# puente_h.net
KiCad netlist of a schematic drawn in EAGLE
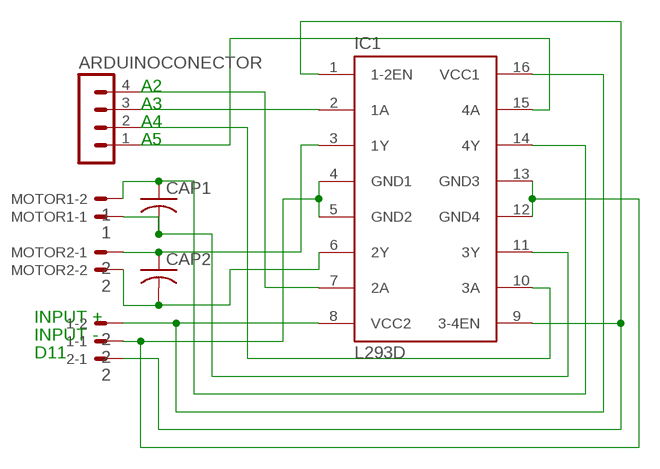
[diagram p0: schematic, sheet 1]

(export (version "E")
  (design (tool "Eeschema 10.0.6"))
  (components
    (comp (ref "1")
      (value "2")
      (footprint "eagle-import:332-02")
      (libsource (lib "eagle-import") (part "332-02"))
    )
    (comp (ref "2")
      (value "2")
      (footprint "eagle-import:332-02")
      (libsource (lib "eagle-import") (part "332-02"))
    )
    (comp (ref "ARDUINOCONECTOR")
      (value "MA04-1")
      (footprint "eagle-import:MA04-1")
      (libsource (lib "eagle-import") (part "MA04-1"))
    )
    (comp (ref "CAP1")
      (value "C-US025-025X050")
      (footprint "eagle-import:C025-025X050")
      (libsource (lib "eagle-import") (part "C-US025-025X050"))
    )
    (comp (ref "CAP2")
      (value "C-US025-025X050")
      (footprint "eagle-import:C025-025X050")
      (libsource (lib "eagle-import") (part "C-US025-025X050"))
    )
    (comp (ref "IC1")
      (value "L293D")
      (footprint "eagle-import:DIL16")
      (libsource (lib "eagle-import") (part "L293D"))
    )
    (comp (ref "MOTOR1")
      (value "1")
      (footprint "eagle-import:332-02")
      (libsource (lib "eagle-import") (part "332-02"))
    )
    (comp (ref "MOTOR2")
      (value "2")
      (footprint "eagle-import:332-02")
      (libsource (lib "eagle-import") (part "332-02"))
    )
  )
  (nets
    (net (code "1") (name "Net-(1A-S)") (class "Default")
      (node (ref "1") (pin "1") (pinfunction "S_1") (pintype "passive"))
      (node (ref "IC1") (pin "12") (pinfunction "GND4_12") (pintype "power_in"))
      (node (ref "IC1") (pin "13") (pinfunction "GND3_13") (pintype "power_in"))
      (node (ref "IC1") (pin "4") (pinfunction "GND1_4") (pintype "power_in"))
      (node (ref "IC1") (pin "5") (pinfunction "GND2_5") (pintype "power_in"))
    )
    (net (code "2") (name "Net-(1B-S)") (class "Default")
      (node (ref "1") (pin "2") (pinfunction "S_2") (pintype "passive"))
      (node (ref "IC1") (pin "16") (pinfunction "VCC1_16") (pintype "power_in"))
      (node (ref "IC1") (pin "8") (pinfunction "VCC2_8") (pintype "power_in"))
    )
    (net (code "3") (name "Net-(2A-S)") (class "Default")
      (node (ref "2") (pin "1") (pinfunction "S_1") (pintype "passive"))
      (node (ref "IC1") (pin "1") (pinfunction "1-2EN_1") (pintype "input"))
      (node (ref "IC1") (pin "9") (pinfunction "3-4EN_9") (pintype "input"))
    )
    (net (code "4") (name "Net-(IC1-1A)") (class "Default")
      (node (ref "ARDUINOCONECTOR") (pin "3") (pinfunction "3_3") (pintype "passive"))
      (node (ref "IC1") (pin "2") (pinfunction "1A_2") (pintype "input"))
    )
    (net (code "5") (name "Net-(IC1-1Y)") (class "Default")
      (node (ref "CAP2") (pin "1") (pinfunction "1_1") (pintype "passive"))
      (node (ref "IC1") (pin "3") (pinfunction "1Y_3") (pintype "output"))
      (node (ref "MOTOR2") (pin "1") (pinfunction "S_1") (pintype "passive"))
    )
    (net (code "6") (name "Net-(IC1-2A)") (class "Default")
      (node (ref "ARDUINOCONECTOR") (pin "4") (pinfunction "4_4") (pintype "passive"))
      (node (ref "IC1") (pin "7") (pinfunction "2A_7") (pintype "input"))
    )
    (net (code "7") (name "Net-(IC1-2Y)") (class "Default")
      (node (ref "CAP2") (pin "2") (pinfunction "2_2") (pintype "passive"))
      (node (ref "IC1") (pin "6") (pinfunction "2Y_6") (pintype "output"))
      (node (ref "MOTOR2") (pin "2") (pinfunction "S_2") (pintype "passive"))
    )
    (net (code "8") (name "Net-(IC1-3A)") (class "Default")
      (node (ref "ARDUINOCONECTOR") (pin "2") (pinfunction "2_2") (pintype "passive"))
      (node (ref "IC1") (pin "10") (pinfunction "3A_10") (pintype "input"))
    )
    (net (code "9") (name "Net-(IC1-3Y)") (class "Default")
      (node (ref "CAP1") (pin "2") (pinfunction "2_2") (pintype "passive"))
      (node (ref "IC1") (pin "11") (pinfunction "3Y_11") (pintype "output"))
      (node (ref "MOTOR1") (pin "1") (pinfunction "S_1") (pintype "passive"))
    )
    (net (code "10") (name "Net-(IC1-4A)") (class "Default")
      (node (ref "ARDUINOCONECTOR") (pin "1") (pinfunction "1_1") (pintype "passive"))
      (node (ref "IC1") (pin "15") (pinfunction "4A_15") (pintype "input"))
    )
    (net (code "11") (name "Net-(IC1-4Y)") (class "Default")
      (node (ref "CAP1") (pin "1") (pinfunction "1_1") (pintype "passive"))
      (node (ref "IC1") (pin "14") (pinfunction "4Y_14") (pintype "output"))
      (node (ref "MOTOR1") (pin "2") (pinfunction "S_2") (pintype "passive"))
    )
  )
)
